# 02_MCU.net
KiCad netlist of a schematic drawn in Altium Designer
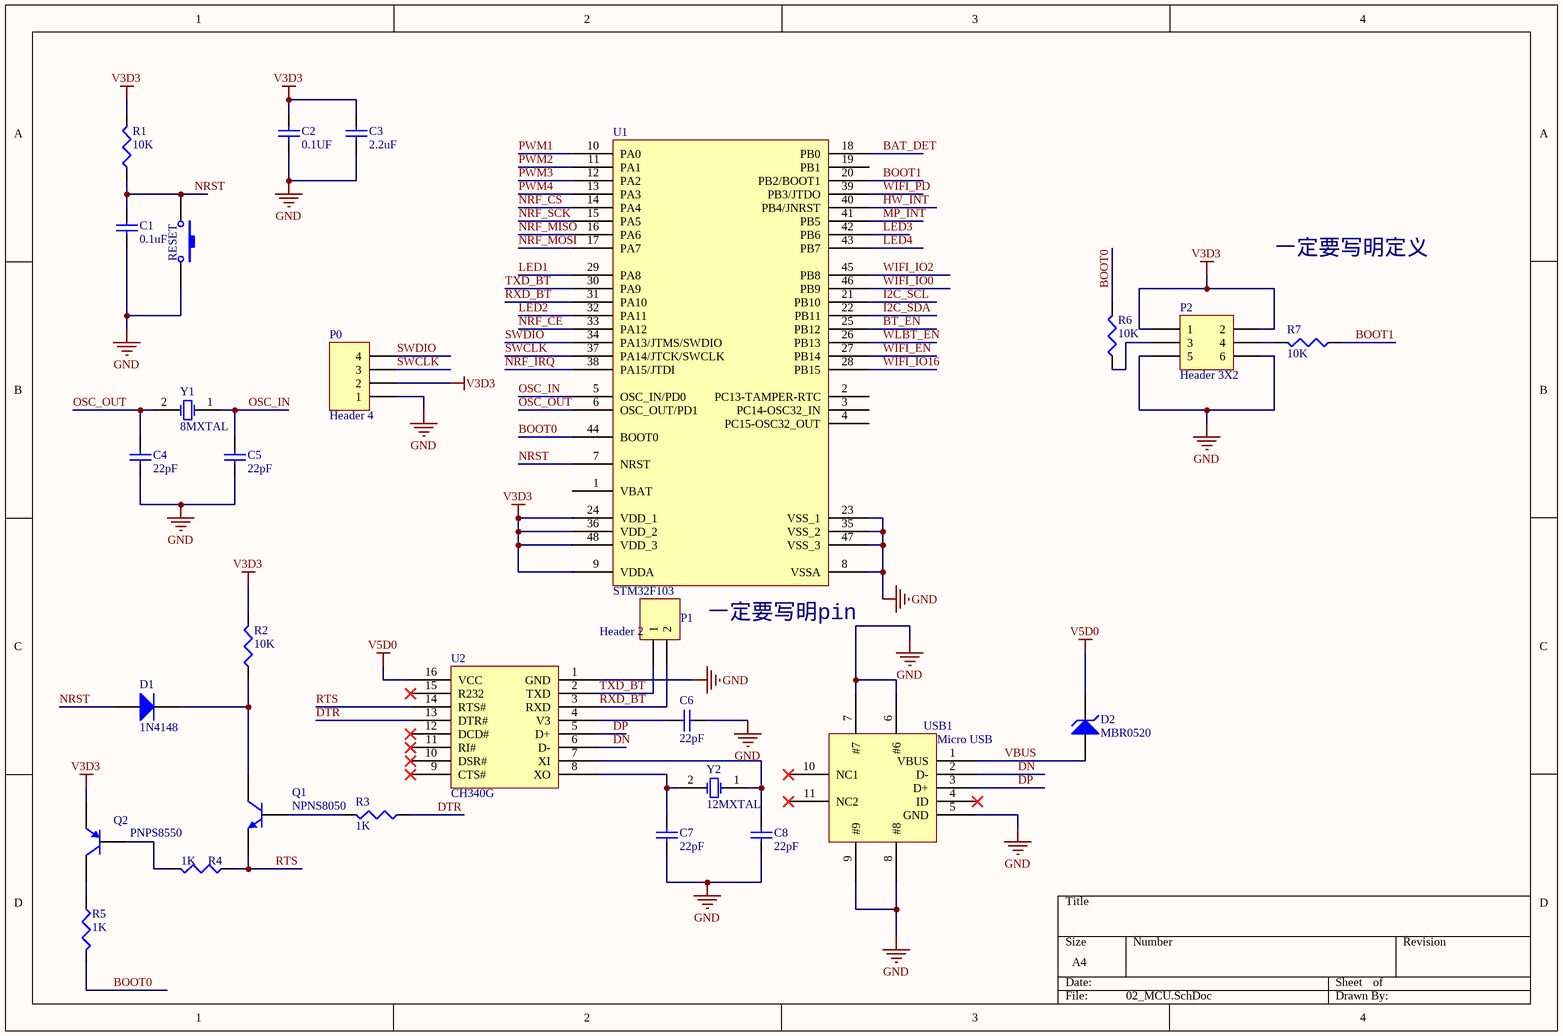
[diagram p0: 02_MCU.SchDoc]

(export (version "E")
  (design (tool "Eeschema 10.0.6"))
  (components
    (comp (ref "C1")
      (value "0.1uF")
      (footprint "0402")
      (description "Capacitor")
      (fields (field (name "Comment") "Cap") (field (name "PUBLISHER") "Altium Limited"))
      (libsource (lib "Miscellaneous Devices") (part "Cap"))
    )
    (comp (ref "C2")
      (value "0.1UF")
      (footprint "0402")
      (description "Capacitor")
      (fields (field (name "Comment") "Cap") (field (name "PUBLISHER") "Altium Limited"))
      (libsource (lib "Miscellaneous Devices") (part "Cap"))
    )
    (comp (ref "C3")
      (value "2.2uF")
      (footprint "0402")
      (description "Capacitor")
      (fields (field (name "Comment") "Cap") (field (name "PUBLISHER") "Altium Limited"))
      (libsource (lib "Miscellaneous Devices") (part "Cap"))
    )
    (comp (ref "C4")
      (value "22pF")
      (footprint "0402")
      (description "Capacitor")
      (fields (field (name "Comment") "Cap") (field (name "PUBLISHER") "Altium Limited"))
      (libsource (lib "Miscellaneous Devices") (part "Cap"))
    )
    (comp (ref "C5")
      (value "22pF")
      (footprint "0402")
      (description "Capacitor")
      (fields (field (name "Comment") "Cap") (field (name "PUBLISHER") "Altium Limited"))
      (libsource (lib "Miscellaneous Devices") (part "Cap"))
    )
    (comp (ref "C6")
      (value "22pF")
      (footprint "0402")
      (description "Capacitor")
      (fields (field (name "Comment") "Cap") (field (name "PUBLISHER") "Altium Limited"))
      (libsource (lib "Miscellaneous Devices") (part "Cap"))
    )
    (comp (ref "C7")
      (value "22pF")
      (footprint "0402")
      (description "Capacitor")
      (fields (field (name "Comment") "Cap") (field (name "PUBLISHER") "Altium Limited"))
      (libsource (lib "Miscellaneous Devices") (part "Cap"))
    )
    (comp (ref "C8")
      (value "22pF")
      (footprint "0402")
      (description "Capacitor")
      (fields (field (name "Comment") "Cap") (field (name "PUBLISHER") "Altium Limited"))
      (libsource (lib "Miscellaneous Devices") (part "Cap"))
    )
    (comp (ref "D1")
      (value "1N4148")
      (footprint "0603")
      (description "High Conductance Fast Diode")
      (fields (field (name "PUBLISHER") "Altium Limited"))
      (libsource (lib "Miscellaneous Devices") (part "Diode 1N4148"))
    )
    (comp (ref "D2")
      (value "MBR0520")
      (footprint "6-0805_N")
      (description "Zener Diode")
      (fields (field (name "PUBLISHER") "Altium Limited"))
      (libsource (lib "Miscellaneous Devices") (part "D Zener"))
    )
    (comp (ref "P0")
      (value "Header 4")
      (footprint "HDR1X4")
      (description "Header, 4-Pin")
      (fields (field (name "PUBLISHER") "Altium Limited"))
      (libsource (lib "Miscellaneous Connectors") (part "Header 4"))
    )
    (comp (ref "P1")
      (value "Header 2")
      (footprint "HDR1X2")
      (description "Header, 2-Pin")
      (fields (field (name "PUBLISHER") "Altium Limited"))
      (libsource (lib "Miscellaneous Connectors") (part "Header 2"))
    )
    (comp (ref "P2")
      (value "Header 3X2")
      (footprint "HDR2X3")
      (description "Header, 3-Pin, Dual row")
      (fields (field (name "PUBLISHER") "Altium Limited"))
      (libsource (lib "Miscellaneous Connectors") (part "Header 3X2"))
    )
    (comp (ref "Q1")
      (value "NPNS8050")
      (footprint "SOT-23_M")
      (description "NPN Bipolar Transistor")
      (fields (field (name "PUBLISHER") "Altium Limited"))
      (libsource (lib "Miscellaneous Devices") (part "NPN"))
    )
    (comp (ref "Q2")
      (value "PNPS8550")
      (footprint "SOT-23_M")
      (description "PNP Bipolar Transistor")
      (fields (field (name "PUBLISHER") "Altium Limited"))
      (libsource (lib "Miscellaneous Devices") (part "PNP"))
    )
    (comp (ref "R1")
      (value "10K")
      (footprint "0402")
      (description "Resistor")
      (fields (field (name "Comment") "Res3") (field (name "PUBLISHER") "Altium Limited"))
      (libsource (lib "Miscellaneous Devices") (part "Res3"))
    )
    (comp (ref "R2")
      (value "10K")
      (footprint "0402")
      (description "Resistor")
      (fields (field (name "Comment") "Res3") (field (name "PUBLISHER") "Altium Limited"))
      (libsource (lib "Miscellaneous Devices") (part "Res3"))
    )
    (comp (ref "R3")
      (value "1K")
      (footprint "0402")
      (description "Resistor")
      (fields (field (name "Comment") "Res3") (field (name "PUBLISHER") "Altium Limited"))
      (libsource (lib "Miscellaneous Devices") (part "Res3"))
    )
    (comp (ref "R4")
      (value "1K")
      (footprint "0402")
      (description "Resistor")
      (fields (field (name "Comment") "Res3") (field (name "PUBLISHER") "Altium Limited"))
      (libsource (lib "Miscellaneous Devices") (part "Res3"))
    )
    (comp (ref "R5")
      (value "1K")
      (footprint "0402")
      (description "Resistor")
      (fields (field (name "Comment") "Res3") (field (name "PUBLISHER") "Altium Limited"))
      (libsource (lib "Miscellaneous Devices") (part "Res3"))
    )
    (comp (ref "R6")
      (value "10K")
      (footprint "0402")
      (description "Resistor")
      (fields (field (name "Comment") "Res3") (field (name "PUBLISHER") "Altium Limited"))
      (libsource (lib "Miscellaneous Devices") (part "Res3"))
    )
    (comp (ref "R7")
      (value "10K")
      (footprint "0402")
      (description "Resistor")
      (fields (field (name "Comment") "Res3") (field (name "PUBLISHER") "Altium Limited"))
      (libsource (lib "Miscellaneous Devices") (part "Res3"))
    )
    (comp (ref "RESET")
      (value "SW-PB")
      (footprint "SWFOOT")
      (description "Switch")
      (fields (field (name "PUBLISHER") "Altium Limited"))
      (libsource (lib "Miscellaneous Devices") (part "SW-PB"))
    )
    (comp (ref "U1")
      (value "STM32F103")
      (footprint "LQFP48S")
      (libsource (lib "aircraftschlib") (part "STM32F103"))
    )
    (comp (ref "U2")
      (value "CH340G")
      (footprint "SSOP16_M")
      (libsource (lib "aircraftschlib") (part "CH340G"))
    )
    (comp (ref "USB1")
      (value "Micro USB")
      (footprint "Micro_USB")
      (libsource (lib "aircraftschlib") (part "Micro USB"))
    )
    (comp (ref "Y1")
      (value "8MXTAL")
      (footprint "XTAL2")
      (description "Crystal Oscillator")
      (fields (field (name "PUBLISHER") "Altium Limited"))
      (libsource (lib "Miscellaneous Devices") (part "XTAL"))
    )
    (comp (ref "Y2")
      (value "12MXTAL")
      (footprint "XTAL2")
      (description "Crystal Oscillator")
      (fields (field (name "PUBLISHER") "Altium Limited"))
      (libsource (lib "Miscellaneous Devices") (part "XTAL"))
    )
  )
  (nets
    (net (code "1") (name "/BAT_DET") (class "Default")
      (node (ref "U1") (pin "18") (pinfunction "PB0_18") (pintype "passive"))
    )
    (net (code "2") (name "/BOOT0") (class "Default")
      (node (ref "R5") (pin "2") (pinfunction "2_2") (pintype "passive"))
      (node (ref "R6") (pin "2") (pinfunction "2_2") (pintype "passive"))
      (node (ref "U1") (pin "44") (pinfunction "BOOT0_44") (pintype "passive"))
    )
    (net (code "3") (name "/BOOT1") (class "Default")
      (node (ref "R7") (pin "1") (pinfunction "1_1") (pintype "passive"))
      (node (ref "U1") (pin "20") (pinfunction "PB2/BOOT1_20") (pintype "passive"))
    )
    (net (code "4") (name "/BT_EN") (class "Default")
      (node (ref "U1") (pin "25") (pinfunction "PB12_25") (pintype "passive"))
    )
    (net (code "5") (name "/DN") (class "Default")
      (node (ref "U2") (pin "6") (pinfunction "D-_6") (pintype "passive"))
      (node (ref "USB1") (pin "2") (pinfunction "D-_2") (pintype "passive"))
    )
    (net (code "6") (name "/DP") (class "Default")
      (node (ref "U2") (pin "5") (pinfunction "D+_5") (pintype "passive"))
      (node (ref "USB1") (pin "3") (pinfunction "D+_3") (pintype "passive"))
    )
    (net (code "7") (name "/DTR") (class "Default")
      (node (ref "R3") (pin "1") (pinfunction "1_1") (pintype "passive"))
      (node (ref "U2") (pin "13") (pinfunction "DTR#_13") (pintype "passive"))
    )
    (net (code "8") (name "/HW_INT") (class "Default")
      (node (ref "U1") (pin "40") (pinfunction "PB4/JNRST_40") (pintype "passive"))
    )
    (net (code "9") (name "/I2C_SCL") (class "Default")
      (node (ref "U1") (pin "21") (pinfunction "PB10_21") (pintype "passive"))
    )
    (net (code "10") (name "/I2C_SDA") (class "Default")
      (node (ref "U1") (pin "22") (pinfunction "PB11_22") (pintype "passive"))
    )
    (net (code "11") (name "/LED1") (class "Default")
      (node (ref "U1") (pin "29") (pinfunction "PA8_29") (pintype "passive"))
    )
    (net (code "12") (name "/LED2") (class "Default")
      (node (ref "U1") (pin "32") (pinfunction "PA11_32") (pintype "passive"))
    )
    (net (code "13") (name "/LED3") (class "Default")
      (node (ref "U1") (pin "42") (pinfunction "PB6_42") (pintype "passive"))
    )
    (net (code "14") (name "/LED4") (class "Default")
      (node (ref "U1") (pin "43") (pinfunction "PB7_43") (pintype "passive"))
    )
    (net (code "15") (name "/MP_INT") (class "Default")
      (node (ref "U1") (pin "41") (pinfunction "PB5_41") (pintype "passive"))
    )
    (net (code "16") (name "/NRF_CE") (class "Default")
      (node (ref "U1") (pin "33") (pinfunction "PA12_33") (pintype "passive"))
    )
    (net (code "17") (name "/NRF_CS") (class "Default")
      (node (ref "U1") (pin "14") (pinfunction "PA4_14") (pintype "passive"))
    )
    (net (code "18") (name "/NRF_IRQ") (class "Default")
      (node (ref "U1") (pin "38") (pinfunction "PA15/JTDI_38") (pintype "passive"))
    )
    (net (code "19") (name "/NRF_MISO") (class "Default")
      (node (ref "U1") (pin "16") (pinfunction "PA6_16") (pintype "passive"))
    )
    (net (code "20") (name "/NRF_MOSI") (class "Default")
      (node (ref "U1") (pin "17") (pinfunction "PA7_17") (pintype "passive"))
    )
    (net (code "21") (name "/NRF_SCK") (class "Default")
      (node (ref "U1") (pin "15") (pinfunction "PA5_15") (pintype "passive"))
    )
    (net (code "22") (name "/NRST") (class "Default")
      (node (ref "C1") (pin "1") (pinfunction "1_1") (pintype "passive"))
      (node (ref "D1") (pin "1") (pinfunction "A_1") (pintype "passive"))
      (node (ref "R1") (pin "1") (pinfunction "1_1") (pintype "passive"))
      (node (ref "RESET") (pin "1") (pinfunction "1_1") (pintype "passive"))
      (node (ref "U1") (pin "7") (pinfunction "NRST_7") (pintype "passive"))
    )
    (net (code "23") (name "/OSC_IN") (class "Default")
      (node (ref "C5") (pin "2") (pinfunction "2_2") (pintype "passive"))
      (node (ref "U1") (pin "5") (pinfunction "OSC_IN/PD0_5") (pintype "passive"))
      (node (ref "Y1") (pin "1") (pinfunction "OSC1_1") (pintype "passive"))
    )
    (net (code "24") (name "/OSC_OUT") (class "Default")
      (node (ref "C4") (pin "1") (pinfunction "1_1") (pintype "passive"))
      (node (ref "U1") (pin "6") (pinfunction "OSC_OUT/PD1_6") (pintype "passive"))
      (node (ref "Y1") (pin "2") (pinfunction "OSC2_2") (pintype "passive"))
    )
    (net (code "25") (name "/PWM1") (class "Default")
      (node (ref "U1") (pin "10") (pinfunction "PA0_10") (pintype "passive"))
    )
    (net (code "26") (name "/PWM2") (class "Default")
      (node (ref "U1") (pin "11") (pinfunction "PA1_11") (pintype "passive"))
    )
    (net (code "27") (name "/PWM3") (class "Default")
      (node (ref "U1") (pin "12") (pinfunction "PA2_12") (pintype "passive"))
    )
    (net (code "28") (name "/PWM4") (class "Default")
      (node (ref "U1") (pin "13") (pinfunction "PA3_13") (pintype "passive"))
    )
    (net (code "29") (name "/RTS") (class "Default")
      (node (ref "Q1") (pin "3") (pinfunction "E_3") (pintype "passive"))
      (node (ref "R4") (pin "1") (pinfunction "1_1") (pintype "passive"))
      (node (ref "U2") (pin "14") (pinfunction "RTS#_14") (pintype "passive"))
    )
    (net (code "30") (name "/RXD_BT") (class "Default")
      (node (ref "P1") (pin "2") (pinfunction "2_2") (pintype "passive"))
      (node (ref "U1") (pin "31") (pinfunction "PA10_31") (pintype "passive"))
      (node (ref "U2") (pin "3") (pinfunction "RXD_3") (pintype "passive"))
    )
    (net (code "31") (name "/SWCLK") (class "Default")
      (node (ref "P0") (pin "3") (pinfunction "3_3") (pintype "passive"))
      (node (ref "U1") (pin "37") (pinfunction "PA14/JTCK/SWCLK_37") (pintype "passive"))
    )
    (net (code "32") (name "/SWDIO") (class "Default")
      (node (ref "P0") (pin "4") (pinfunction "4_4") (pintype "passive"))
      (node (ref "U1") (pin "34") (pinfunction "PA13/JTMS/SWDIO_34") (pintype "passive"))
    )
    (net (code "33") (name "/TXD_BT") (class "Default")
      (node (ref "P1") (pin "1") (pinfunction "1_1") (pintype "passive"))
      (node (ref "U1") (pin "30") (pinfunction "PA9_30") (pintype "passive"))
      (node (ref "U2") (pin "2") (pinfunction "TXD_2") (pintype "passive"))
    )
    (net (code "34") (name "/VBUS") (class "Default")
      (node (ref "D2") (pin "1") (pinfunction "A_1") (pintype "passive"))
      (node (ref "USB1") (pin "1") (pinfunction "VBUS_1") (pintype "passive"))
    )
    (net (code "35") (name "/WIFI_EN") (class "Default")
      (node (ref "U1") (pin "27") (pinfunction "PB14_27") (pintype "passive"))
    )
    (net (code "36") (name "/WIFI_IO0") (class "Default")
      (node (ref "U1") (pin "46") (pinfunction "PB9_46") (pintype "passive"))
    )
    (net (code "37") (name "/WIFI_IO2") (class "Default")
      (node (ref "U1") (pin "45") (pinfunction "PB8_45") (pintype "passive"))
    )
    (net (code "38") (name "/WIFI_IO16") (class "Default")
      (node (ref "U1") (pin "28") (pinfunction "PB15_28") (pintype "passive"))
    )
    (net (code "39") (name "/WIFI_PD") (class "Default")
      (node (ref "U1") (pin "39") (pinfunction "PB3/JTDO_39") (pintype "passive"))
    )
    (net (code "40") (name "/WLBT_EN") (class "Default")
      (node (ref "U1") (pin "26") (pinfunction "PB13_26") (pintype "passive"))
    )
    (net (code "41") (name "GND") (class "Default")
      (node (ref "C1") (pin "2") (pinfunction "2_2") (pintype "passive"))
      (node (ref "C2") (pin "2") (pinfunction "2_2") (pintype "passive"))
      (node (ref "C3") (pin "2") (pinfunction "2_2") (pintype "passive"))
      (node (ref "C4") (pin "2") (pinfunction "2_2") (pintype "passive"))
      (node (ref "C5") (pin "1") (pinfunction "1_1") (pintype "passive"))
      (node (ref "C6") (pin "1") (pinfunction "1_1") (pintype "passive"))
      (node (ref "C7") (pin "2") (pinfunction "2_2") (pintype "passive"))
      (node (ref "C8") (pin "1") (pinfunction "1_1") (pintype "passive"))
      (node (ref "P0") (pin "1") (pinfunction "1_1") (pintype "passive"))
      (node (ref "P2") (pin "5") (pinfunction "5_5") (pintype "passive"))
      (node (ref "P2") (pin "6") (pinfunction "6_6") (pintype "passive"))
      (node (ref "RESET") (pin "2") (pinfunction "2_2") (pintype "passive"))
      (node (ref "U1") (pin "23") (pinfunction "VSS_1_23") (pintype "passive"))
      (node (ref "U1") (pin "35") (pinfunction "VSS_2_35") (pintype "passive"))
      (node (ref "U1") (pin "47") (pinfunction "VSS_3_47") (pintype "passive"))
      (node (ref "U1") (pin "8") (pinfunction "VSSA_8") (pintype "passive"))
      (node (ref "U2") (pin "1") (pinfunction "GND_1") (pintype "passive"))
      (node (ref "USB1") (pin "5") (pinfunction "GND_5") (pintype "passive"))
      (node (ref "USB1") (pin "6") (pinfunction "#6_6") (pintype "passive"))
      (node (ref "USB1") (pin "7") (pinfunction "#7_7") (pintype "passive"))
      (node (ref "USB1") (pin "8") (pinfunction "#8_8") (pintype "passive"))
      (node (ref "USB1") (pin "9") (pinfunction "#9_9") (pintype "passive"))
    )
    (net (code "42") (name "Net-(D1-K)") (class "Default")
      (node (ref "D1") (pin "2") (pinfunction "K_2") (pintype "passive"))
      (node (ref "Q1") (pin "1") (pinfunction "C_1") (pintype "passive"))
      (node (ref "R2") (pin "1") (pinfunction "1_1") (pintype "passive"))
    )
    (net (code "43") (name "Net-(P2-Pad3)") (class "Default")
      (node (ref "P2") (pin "3") (pinfunction "3_3") (pintype "passive"))
      (node (ref "R6") (pin "1") (pinfunction "1_1") (pintype "passive"))
    )
    (net (code "44") (name "Net-(P2-Pad4)") (class "Default")
      (node (ref "P2") (pin "4") (pinfunction "4_4") (pintype "passive"))
      (node (ref "R7") (pin "2") (pinfunction "2_2") (pintype "passive"))
    )
    (net (code "45") (name "Net-(Q1-B)") (class "Default")
      (node (ref "Q1") (pin "2") (pinfunction "B_2") (pintype "passive"))
      (node (ref "R3") (pin "2") (pinfunction "2_2") (pintype "passive"))
    )
    (net (code "46") (name "Net-(Q2-B)") (class "Default")
      (node (ref "Q2") (pin "2") (pinfunction "B_2") (pintype "passive"))
      (node (ref "R4") (pin "2") (pinfunction "2_2") (pintype "passive"))
    )
    (net (code "47") (name "Net-(Q2-C)") (class "Default")
      (node (ref "Q2") (pin "1") (pinfunction "C_1") (pintype "passive"))
      (node (ref "R5") (pin "1") (pinfunction "1_1") (pintype "passive"))
    )
    (net (code "48") (name "Net-(U2-V3)") (class "Default")
      (node (ref "C6") (pin "2") (pinfunction "2_2") (pintype "passive"))
      (node (ref "U2") (pin "4") (pinfunction "V3_4") (pintype "passive"))
    )
    (net (code "49") (name "Net-(U2-XI)") (class "Default")
      (node (ref "C8") (pin "2") (pinfunction "2_2") (pintype "passive"))
      (node (ref "U2") (pin "7") (pinfunction "XI_7") (pintype "passive"))
      (node (ref "Y2") (pin "1") (pinfunction "OSC1_1") (pintype "passive"))
    )
    (net (code "50") (name "Net-(U2-XO)") (class "Default")
      (node (ref "C7") (pin "1") (pinfunction "1_1") (pintype "passive"))
      (node (ref "U2") (pin "8") (pinfunction "XO_8") (pintype "passive"))
      (node (ref "Y2") (pin "2") (pinfunction "OSC2_2") (pintype "passive"))
    )
    (net (code "51") (name "V3D3") (class "Default")
      (node (ref "C2") (pin "1") (pinfunction "1_1") (pintype "passive"))
      (node (ref "C3") (pin "1") (pinfunction "1_1") (pintype "passive"))
      (node (ref "P0") (pin "2") (pinfunction "2_2") (pintype "passive"))
      (node (ref "P2") (pin "1") (pinfunction "1_1") (pintype "passive"))
      (node (ref "P2") (pin "2") (pinfunction "2_2") (pintype "passive"))
      (node (ref "Q2") (pin "3") (pinfunction "E_3") (pintype "passive"))
      (node (ref "R1") (pin "2") (pinfunction "2_2") (pintype "passive"))
      (node (ref "R2") (pin "2") (pinfunction "2_2") (pintype "passive"))
      (node (ref "U1") (pin "24") (pinfunction "VDD_1_24") (pintype "passive"))
      (node (ref "U1") (pin "36") (pinfunction "VDD_2_36") (pintype "passive"))
      (node (ref "U1") (pin "48") (pinfunction "VDD_3_48") (pintype "passive"))
      (node (ref "U1") (pin "9") (pinfunction "VDDA_9") (pintype "passive"))
    )
    (net (code "52") (name "V5D0") (class "Default")
      (node (ref "D2") (pin "2") (pinfunction "K_2") (pintype "passive"))
      (node (ref "U2") (pin "16") (pinfunction "VCC_16") (pintype "passive"))
    )
    (net (code "53") (name "unconnected-(U1-PB1-Pad19)") (class "Default")
      (node (ref "U1") (pin "19") (pinfunction "PB1_19") (pintype "passive"))
    )
    (net (code "54") (name "unconnected-(U1-PC13-TAMPER-RTC-Pad2)") (class "Default")
      (node (ref "U1") (pin "2") (pinfunction "PC13-TAMPER-RTC_2") (pintype "passive"))
    )
    (net (code "55") (name "unconnected-(U1-PC14-OSC32_IN-Pad3)") (class "Default")
      (node (ref "U1") (pin "3") (pinfunction "PC14-OSC32_IN_3") (pintype "passive"))
    )
    (net (code "56") (name "unconnected-(U1-PC15-OSC32_OUT-Pad4)") (class "Default")
      (node (ref "U1") (pin "4") (pinfunction "PC15-OSC32_OUT_4") (pintype "passive"))
    )
    (net (code "57") (name "unconnected-(U1-VBAT-Pad1)") (class "Default")
      (node (ref "U1") (pin "1") (pinfunction "VBAT_1") (pintype "passive"))
    )
    (net (code "58") (name "unconnected-(U2-CTS#-Pad9)") (class "Default")
      (node (ref "U2") (pin "9") (pinfunction "CTS#_9") (pintype "passive+no_connect"))
    )
    (net (code "59") (name "unconnected-(U2-DCD#-Pad12)") (class "Default")
      (node (ref "U2") (pin "12") (pinfunction "DCD#_12") (pintype "passive+no_connect"))
    )
    (net (code "60") (name "unconnected-(U2-DSR#-Pad10)") (class "Default")
      (node (ref "U2") (pin "10") (pinfunction "DSR#_10") (pintype "passive+no_connect"))
    )
    (net (code "61") (name "unconnected-(U2-R232-Pad15)") (class "Default")
      (node (ref "U2") (pin "15") (pinfunction "R232_15") (pintype "passive+no_connect"))
    )
    (net (code "62") (name "unconnected-(U2-RI#-Pad11)") (class "Default")
      (node (ref "U2") (pin "11") (pinfunction "RI#_11") (pintype "passive+no_connect"))
    )
    (net (code "63") (name "unconnected-(USB1-ID-Pad4)") (class "Default")
      (node (ref "USB1") (pin "4") (pinfunction "ID_4") (pintype "passive+no_connect"))
    )
    (net (code "64") (name "unconnected-(USB1-NC1-Pad10)") (class "Default")
      (node (ref "USB1") (pin "10") (pinfunction "NC1_10") (pintype "passive+no_connect"))
    )
    (net (code "65") (name "unconnected-(USB1-NC2-Pad11)") (class "Default")
      (node (ref "USB1") (pin "11") (pinfunction "NC2_11") (pintype "passive+no_connect"))
    )
  )
)
